# pll_schematic.net
KiCad netlist of a schematic drawn in Altium Designer
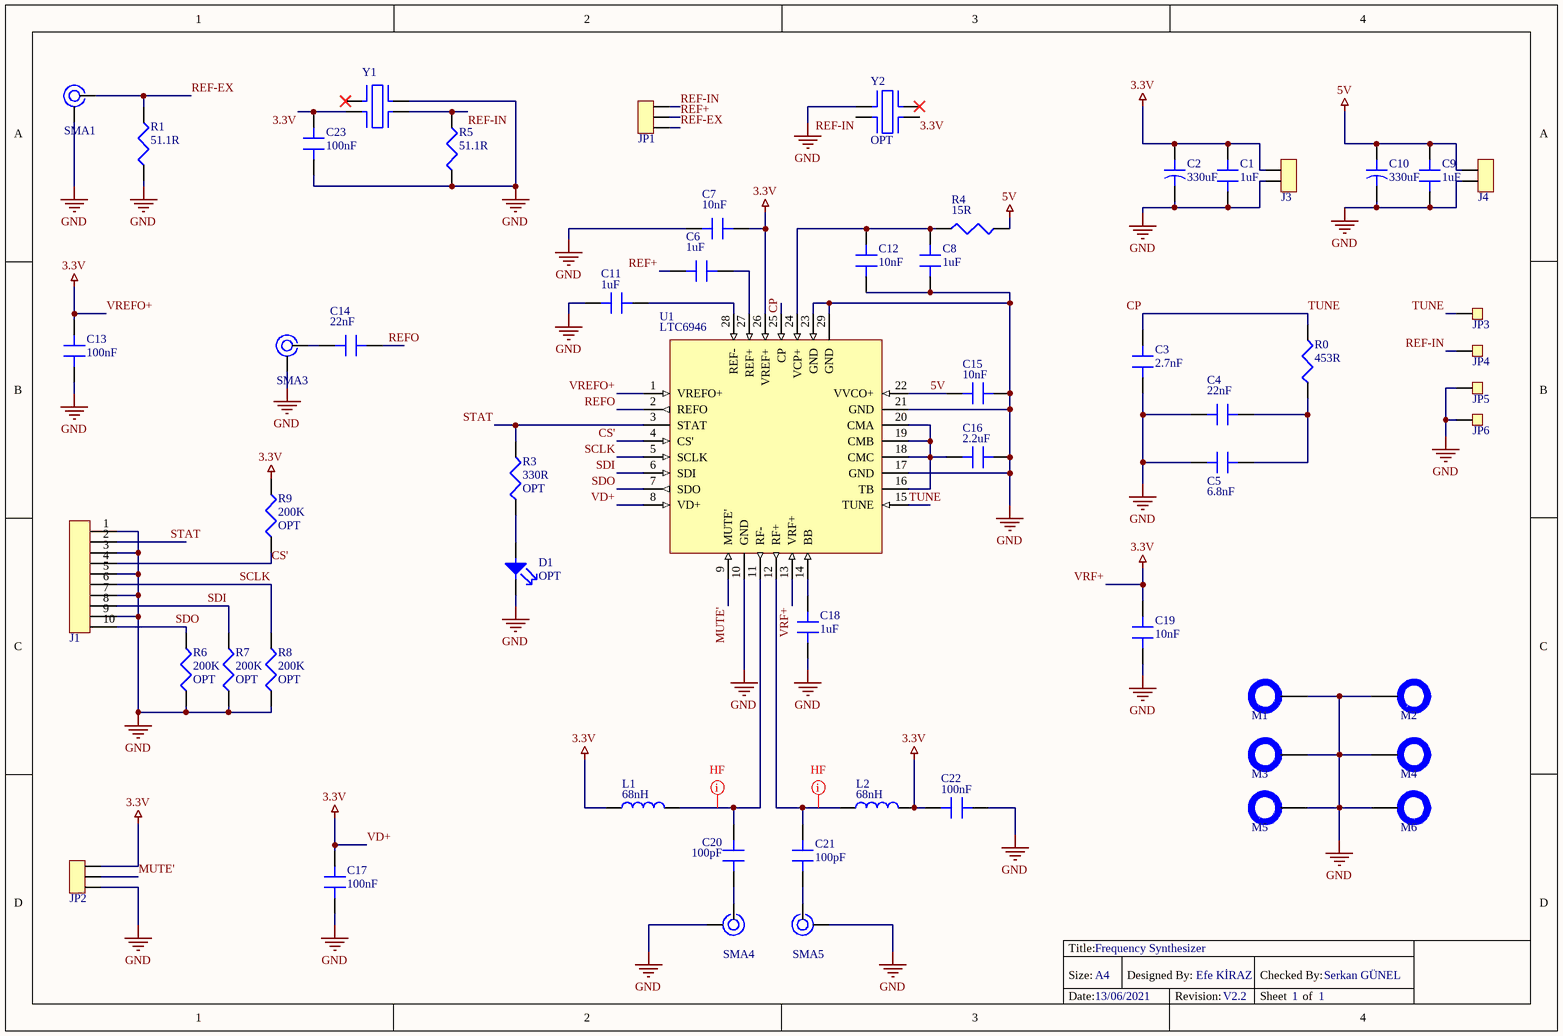
[diagram p0: pll_schematic.SchDoc]

(export (version "E")
  (design (tool "Eeschema 10.0.6"))
  (components
    (comp (ref "C1") (value "1uF") (footprint "C0603") (libsource (lib "pll_schematic_lib") (part "C")))
    (comp (ref "C2") (value "330uF") (footprint "C_TANT_D") (libsource (lib "pll_schematic_lib") (part "CP")))
    (comp (ref "C3") (value "2.7nF") (footprint "C0603") (libsource (lib "pll_schematic_lib") (part "C")))
    (comp (ref "C4") (value "22nF") (footprint "C0603") (libsource (lib "pll_schematic_lib") (part "C")))
    (comp (ref "C5") (value "6.8nF") (footprint "C0603") (libsource (lib "pll_schematic_lib") (part "C")))
    (comp (ref "C6") (value "1uF") (footprint "C0603") (libsource (lib "pll_schematic_lib") (part "C")))
    (comp (ref "C7") (value "10nF") (footprint "C0603") (libsource (lib "pll_schematic_lib") (part "C")))
    (comp (ref "C8") (value "1uF") (footprint "C0603") (libsource (lib "pll_schematic_lib") (part "C")))
    (comp (ref "C9") (value "1uF") (footprint "C0603") (libsource (lib "pll_schematic_lib") (part "C")))
    (comp (ref "C10")
      (value "330uF")
      (footprint "C_TANT_D")
      (libsource (lib "pll_schematic_lib") (part "CP"))
    )
    (comp (ref "C11") (value "1uF") (footprint "C0603") (libsource (lib "pll_schematic_lib") (part "C")))
    (comp (ref "C12") (value "10nF") (footprint "C0603") (libsource (lib "pll_schematic_lib") (part "C")))
    (comp (ref "C13") (value "100nF") (footprint "C0603") (libsource (lib "pll_schematic_lib") (part "C")))
    (comp (ref "C14") (value "22nF") (footprint "C0603") (libsource (lib "pll_schematic_lib") (part "C")))
    (comp (ref "C15") (value "10nF") (footprint "C0603") (libsource (lib "pll_schematic_lib") (part "C")))
    (comp (ref "C16") (value "2.2uF") (footprint "C0805") (libsource (lib "pll_schematic_lib") (part "C")))
    (comp (ref "C17") (value "100nF") (footprint "C0603") (libsource (lib "pll_schematic_lib") (part "C")))
    (comp (ref "C18") (value "1uF") (footprint "C0603") (libsource (lib "pll_schematic_lib") (part "C")))
    (comp (ref "C19") (value "10nF") (footprint "C0603") (libsource (lib "pll_schematic_lib") (part "C")))
    (comp (ref "C20") (value "100pF") (footprint "C0603") (libsource (lib "pll_schematic_lib") (part "C")))
    (comp (ref "C21") (value "100pF") (footprint "C0603") (libsource (lib "pll_schematic_lib") (part "C")))
    (comp (ref "C22") (value "100nF") (footprint "C0603") (libsource (lib "pll_schematic_lib") (part "C")))
    (comp (ref "C23") (value "100nF") (footprint "C0603") (libsource (lib "pll_schematic_lib") (part "C")))
    (comp (ref "D1")
      (value "-")
      (footprint "D0805")
      (fields (field (name "ASSEMBLY") "OPT"))
      (libsource (lib "pll_schematic_lib") (part "LED"))
    )
    (comp (ref "J1")
      (value "-")
      (footprint "IDC-2x05")
      (libsource (lib "pll_schematic_lib") (part "Conn_Gene_1x10"))
    )
    (comp (ref "J3")
      (value "-")
      (footprint "JST_XH_A_2")
      (libsource (lib "pll_schematic_lib") (part "Conn_Gene_1x02"))
    )
    (comp (ref "J4")
      (value "-")
      (footprint "JST_XH_A_2")
      (libsource (lib "pll_schematic_lib") (part "Conn_Gene_1x02"))
    )
    (comp (ref "JP1")
      (value "-")
      (footprint "PIN_HEADER_1x03")
      (libsource (lib "pll_schematic_lib") (part "Pin Header 1x03"))
    )
    (comp (ref "JP2")
      (value "-")
      (footprint "PIN_HEADER_1x03")
      (libsource (lib "pll_schematic_lib") (part "Pin Header 1x03"))
    )
    (comp (ref "JP3")
      (value "-")
      (footprint "PIN_HEADER_1X01")
      (libsource (lib "pll_schematic_lib") (part "Pin Header 1x01"))
    )
    (comp (ref "JP4")
      (value "-")
      (footprint "PIN_HEADER_1X01")
      (libsource (lib "pll_schematic_lib") (part "Pin Header 1x01"))
    )
    (comp (ref "JP5")
      (value "-")
      (footprint "PIN_HEADER_1X01")
      (libsource (lib "pll_schematic_lib") (part "Pin Header 1x01"))
    )
    (comp (ref "JP6")
      (value "-")
      (footprint "PIN_HEADER_1X01")
      (libsource (lib "pll_schematic_lib") (part "Pin Header 1x01"))
    )
    (comp (ref "L1") (value "68nH") (footprint "L0402") (libsource (lib "pll_schematic_lib") (part "L")))
    (comp (ref "L2") (value "68nH") (footprint "L0402") (libsource (lib "pll_schematic_lib") (part "L")))
    (comp (ref "M1")
      (value "MOUNTING_HOLE")
      (footprint "MOUNTING_HOLE_NP_M3")
      (description "Non-Plated")
      (libsource (lib "pll_schematic_lib") (part "MOUNTING_HOLE"))
    )
    (comp (ref "M2")
      (value "MOUNTING_HOLE")
      (footprint "MOUNTING_HOLE_NP_M3")
      (description "Non-Plated")
      (libsource (lib "pll_schematic_lib") (part "MOUNTING_HOLE"))
    )
    (comp (ref "M3")
      (value "MOUNTING_HOLE")
      (footprint "MOUNTING_HOLE_NP_M3")
      (description "Non-Plated")
      (libsource (lib "pll_schematic_lib") (part "MOUNTING_HOLE"))
    )
    (comp (ref "M4")
      (value "MOUNTING_HOLE")
      (footprint "MOUNTING_HOLE_NP_M3")
      (description "Non-Plated")
      (libsource (lib "pll_schematic_lib") (part "MOUNTING_HOLE"))
    )
    (comp (ref "M5")
      (value "MOUNTING_HOLE")
      (footprint "MOUNTING_HOLE_NP_M3")
      (description "Non-Plated")
      (libsource (lib "pll_schematic_lib") (part "MOUNTING_HOLE"))
    )
    (comp (ref "M6")
      (value "MOUNTING_HOLE")
      (footprint "MOUNTING_HOLE_NP_M3")
      (description "Non-Plated")
      (libsource (lib "pll_schematic_lib") (part "MOUNTING_HOLE"))
    )
    (comp (ref "R0") (value "453R") (footprint "R0603") (libsource (lib "pll_schematic_lib") (part "R")))
    (comp (ref "R1") (value "51.1R") (footprint "R0603") (libsource (lib "pll_schematic_lib") (part "R")))
    (comp (ref "R3")
      (value "330R")
      (footprint "R0603")
      (fields (field (name "ASSEMBLY") "OPT"))
      (libsource (lib "pll_schematic_lib") (part "R"))
    )
    (comp (ref "R4") (value "15R") (footprint "R0603") (libsource (lib "pll_schematic_lib") (part "R")))
    (comp (ref "R5") (value "51.1R") (footprint "R0603") (libsource (lib "pll_schematic_lib") (part "R")))
    (comp (ref "R6")
      (value "200K")
      (footprint "R0603")
      (description "OPT")
      (fields (field (name "ASSEMBLY") "OPT"))
      (libsource (lib "pll_schematic_lib") (part "R"))
    )
    (comp (ref "R7")
      (value "200K")
      (footprint "R0603")
      (description "OPT")
      (fields (field (name "ASSEMBLY") "OPT"))
      (libsource (lib "pll_schematic_lib") (part "R"))
    )
    (comp (ref "R8")
      (value "200K")
      (footprint "R0603")
      (description "OPT")
      (fields (field (name "ASSEMBLY") "OPT"))
      (libsource (lib "pll_schematic_lib") (part "R"))
    )
    (comp (ref "R9")
      (value "200K")
      (footprint "R0603")
      (description "OPT")
      (fields (field (name "ASSEMBLY") "OPT"))
      (libsource (lib "pll_schematic_lib") (part "R"))
    )
    (comp (ref "SMA1") (value "-") (footprint "SMA") (libsource (lib "pll_schematic_lib") (part "SMA")))
    (comp (ref "SMA3") (value "-") (footprint "SMA") (libsource (lib "pll_schematic_lib") (part "SMA")))
    (comp (ref "SMA4") (value "-") (footprint "SMA") (libsource (lib "") (part "SMA_1")))
    (comp (ref "SMA5") (value "-") (footprint "SMA") (libsource (lib "pll_schematic_lib") (part "SMA")))
    (comp (ref "U1")
      (value "LTC6946")
      (footprint "QFN50P400X500X80_HS-29N_2")
      (libsource (lib "pll_schematic_lib") (part "LTC6946IUFD-1#PBF-ND"))
    )
    (comp (ref "Y1") (value "-") (footprint "XOSC") (libsource (lib "pll_schematic_lib") (part "OSC")))
    (comp (ref "Y2")
      (value "OPT")
      (footprint "XOSC_SMD")
      (libsource (lib "pll_schematic_lib") (part "OSC_SMD"))
    )
  )
  (nets
    (net (code "1") (name "/CP") (class "Default")
      (node (ref "C3") (pin "2") (pinfunction "-_2") (pintype "passive"))
      (node (ref "JP3") (pin "1") (pinfunction "-_1") (pintype "passive"))
      (node (ref "R0") (pin "2") (pinfunction "-_2") (pintype "passive"))
      (node (ref "U1") (pin "15") (pinfunction "TUNE_15") (pintype "input"))
      (node (ref "U1") (pin "25") (pinfunction "CP_25") (pintype "input"))
    )
    (net (code "2") (name "/CS'") (class "Default")
      (node (ref "J1") (pin "4") (pinfunction "*_4") (pintype "passive"))
      (node (ref "R9") (pin "1") (pinfunction "-_1") (pintype "passive"))
      (node (ref "U1") (pin "4") (pinfunction "CS'_4") (pintype "input"))
    )
    (net (code "3") (name "/MUTE'") (class "Default")
      (node (ref "JP2") (pin "2") (pinfunction "-_2") (pintype "passive"))
      (node (ref "U1") (pin "9") (pinfunction "MUTE'_9") (pintype "input"))
    )
    (net (code "4") (name "/REF+") (class "Default")
      (node (ref "C6") (pin "1") (pinfunction "-_1") (pintype "passive"))
      (node (ref "JP1") (pin "2") (pinfunction "-_2") (pintype "passive"))
    )
    (net (code "5") (name "/REF-EX") (class "Default")
      (node (ref "JP1") (pin "3") (pinfunction "-_3") (pintype "passive"))
      (node (ref "R1") (pin "2") (pinfunction "-_2") (pintype "passive"))
      (node (ref "SMA1") (pin "1") (pinfunction "-_1") (pintype "passive"))
    )
    (net (code "6") (name "/REF-IN") (class "Default")
      (node (ref "JP1") (pin "1") (pinfunction "-_1") (pintype "passive"))
      (node (ref "JP4") (pin "1") (pinfunction "-_1") (pintype "passive"))
      (node (ref "R5") (pin "2") (pinfunction "-_2") (pintype "passive"))
      (node (ref "Y1") (pin "5") (pinfunction "5_5") (pintype "passive"))
      (node (ref "Y2") (pin "3") (pinfunction "3_3") (pintype "passive"))
    )
    (net (code "7") (name "/REFO") (class "Default")
      (node (ref "C14") (pin "2") (pinfunction "-_2") (pintype "passive"))
      (node (ref "U1") (pin "2") (pinfunction "REFO_2") (pintype "output"))
    )
    (net (code "8") (name "/SCLK") (class "Default")
      (node (ref "J1") (pin "6") (pinfunction "*_6") (pintype "passive"))
      (node (ref "R8") (pin "2") (pinfunction "-_2") (pintype "passive"))
      (node (ref "U1") (pin "5") (pinfunction "SCLK_5") (pintype "input"))
    )
    (net (code "9") (name "/SDI") (class "Default")
      (node (ref "J1") (pin "8") (pinfunction "*_8") (pintype "passive"))
      (node (ref "R7") (pin "2") (pinfunction "-_2") (pintype "passive"))
      (node (ref "U1") (pin "6") (pinfunction "SDI_6") (pintype "input"))
    )
    (net (code "10") (name "/SDO") (class "Default")
      (node (ref "J1") (pin "10") (pinfunction "*_10") (pintype "passive"))
      (node (ref "R6") (pin "2") (pinfunction "-_2") (pintype "passive"))
      (node (ref "U1") (pin "7") (pinfunction "SDO_7") (pintype "output"))
    )
    (net (code "11") (name "/STAT") (class "Default")
      (node (ref "J1") (pin "2") (pinfunction "*_2") (pintype "passive"))
      (node (ref "R3") (pin "2") (pinfunction "-_2") (pintype "passive"))
      (node (ref "U1") (pin "3") (pinfunction "STAT_3") (pintype "passive"))
    )
    (net (code "12") (name "3.3V") (class "Default")
      (node (ref "C1") (pin "2") (pinfunction "-_2") (pintype "passive"))
      (node (ref "C13") (pin "2") (pinfunction "-_2") (pintype "passive"))
      (node (ref "C17") (pin "2") (pinfunction "-_2") (pintype "passive"))
      (node (ref "C19") (pin "2") (pinfunction "-_2") (pintype "passive"))
      (node (ref "C2") (pin "1") (pinfunction "-_1") (pintype "passive"))
      (node (ref "C22") (pin "1") (pinfunction "-_1") (pintype "passive"))
      (node (ref "C23") (pin "2") (pinfunction "-_2") (pintype "passive"))
      (node (ref "C7") (pin "1") (pinfunction "-_1") (pintype "passive"))
      (node (ref "J3") (pin "1") (pinfunction "-_1") (pintype "passive"))
      (node (ref "JP2") (pin "1") (pinfunction "-_1") (pintype "passive"))
      (node (ref "L1") (pin "1") (pinfunction "-_1") (pintype "passive"))
      (node (ref "L2") (pin "2") (pinfunction "-_2") (pintype "passive"))
      (node (ref "R9") (pin "2") (pinfunction "-_2") (pintype "passive"))
      (node (ref "U1") (pin "1") (pinfunction "VREFO+_1") (pintype "input"))
      (node (ref "U1") (pin "13") (pinfunction "VRF+_13") (pintype "input"))
      (node (ref "U1") (pin "26") (pinfunction "VREF+_26") (pintype "input"))
      (node (ref "U1") (pin "8") (pinfunction "VD+_8") (pintype "input"))
      (node (ref "Y1") (pin "8") (pinfunction "8_8") (pintype "passive"))
      (node (ref "Y2") (pin "4") (pinfunction "4_4") (pintype "passive"))
    )
    (net (code "13") (name "5V") (class "Default")
      (node (ref "C10") (pin "1") (pinfunction "-_1") (pintype "passive"))
      (node (ref "C15") (pin "1") (pinfunction "-_1") (pintype "passive"))
      (node (ref "C9") (pin "1") (pinfunction "-_1") (pintype "passive"))
      (node (ref "J4") (pin "1") (pinfunction "-_1") (pintype "passive"))
      (node (ref "R4") (pin "2") (pinfunction "-_2") (pintype "passive"))
      (node (ref "U1") (pin "22") (pinfunction "VVCO+_22") (pintype "input"))
    )
    (net (code "14") (name "GND") (class "Default")
      (node (ref "C1") (pin "1") (pinfunction "-_1") (pintype "passive"))
      (node (ref "C10") (pin "2") (pinfunction "-_2") (pintype "passive"))
      (node (ref "C11") (pin "1") (pinfunction "-_1") (pintype "passive"))
      (node (ref "C12") (pin "2") (pinfunction "-_2") (pintype "passive"))
      (node (ref "C13") (pin "1") (pinfunction "-_1") (pintype "passive"))
      (node (ref "C15") (pin "2") (pinfunction "-_2") (pintype "passive"))
      (node (ref "C16") (pin "2") (pinfunction "-_2") (pintype "passive"))
      (node (ref "C17") (pin "1") (pinfunction "-_1") (pintype "passive"))
      (node (ref "C18") (pin "1") (pinfunction "-_1") (pintype "passive"))
      (node (ref "C19") (pin "1") (pinfunction "-_1") (pintype "passive"))
      (node (ref "C2") (pin "2") (pinfunction "-_2") (pintype "passive"))
      (node (ref "C22") (pin "2") (pinfunction "-_2") (pintype "passive"))
      (node (ref "C23") (pin "1") (pinfunction "-_1") (pintype "passive"))
      (node (ref "C3") (pin "1") (pinfunction "-_1") (pintype "passive"))
      (node (ref "C4") (pin "2") (pinfunction "-_2") (pintype "passive"))
      (node (ref "C5") (pin "2") (pinfunction "-_2") (pintype "passive"))
      (node (ref "C7") (pin "2") (pinfunction "-_2") (pintype "passive"))
      (node (ref "C8") (pin "1") (pinfunction "-_1") (pintype "passive"))
      (node (ref "C9") (pin "2") (pinfunction "-_2") (pintype "passive"))
      (node (ref "D1") (pin "C") (pinfunction "C_C") (pintype "passive"))
      (node (ref "J1") (pin "1") (pinfunction "*_1") (pintype "passive"))
      (node (ref "J1") (pin "3") (pinfunction "*_3") (pintype "passive"))
      (node (ref "J1") (pin "5") (pinfunction "*_5") (pintype "passive"))
      (node (ref "J1") (pin "7") (pinfunction "*_7") (pintype "passive"))
      (node (ref "J1") (pin "9") (pinfunction "*_9") (pintype "passive"))
      (node (ref "J3") (pin "2") (pinfunction "-_2") (pintype "passive"))
      (node (ref "J4") (pin "2") (pinfunction "-_2") (pintype "passive"))
      (node (ref "JP2") (pin "3") (pinfunction "-_3") (pintype "passive"))
      (node (ref "JP5") (pin "1") (pinfunction "-_1") (pintype "passive"))
      (node (ref "JP6") (pin "1") (pinfunction "-_1") (pintype "passive"))
      (node (ref "M1") (pin "1") (pinfunction "*_1") (pintype "passive"))
      (node (ref "M2") (pin "1") (pinfunction "*_1") (pintype "passive"))
      (node (ref "M3") (pin "1") (pinfunction "*_1") (pintype "passive"))
      (node (ref "M4") (pin "1") (pinfunction "*_1") (pintype "passive"))
      (node (ref "M5") (pin "1") (pinfunction "*_1") (pintype "passive"))
      (node (ref "M6") (pin "1") (pinfunction "*_1") (pintype "passive"))
      (node (ref "R1") (pin "1") (pinfunction "-_1") (pintype "passive"))
      (node (ref "R5") (pin "1") (pinfunction "-_1") (pintype "passive"))
      (node (ref "R6") (pin "1") (pinfunction "-_1") (pintype "passive"))
      (node (ref "R7") (pin "1") (pinfunction "-_1") (pintype "passive"))
      (node (ref "R8") (pin "1") (pinfunction "-_1") (pintype "passive"))
      (node (ref "SMA1") (pin "2") (pinfunction "-_2") (pintype "passive"))
      (node (ref "SMA3") (pin "2") (pinfunction "-_2") (pintype "passive"))
      (node (ref "SMA4") (pin "2") (pinfunction "-_2") (pintype "passive"))
      (node (ref "SMA5") (pin "2") (pinfunction "-_2") (pintype "passive"))
      (node (ref "U1") (pin "10") (pinfunction "GND_10") (pintype "passive"))
      (node (ref "U1") (pin "17") (pinfunction "GND_17") (pintype "passive"))
      (node (ref "U1") (pin "21") (pinfunction "GND_21") (pintype "passive"))
      (node (ref "U1") (pin "23") (pinfunction "GND_23") (pintype "input"))
      (node (ref "U1") (pin "29") (pinfunction "GND_29") (pintype "passive"))
      (node (ref "Y1") (pin "4") (pinfunction "4_4") (pintype "passive"))
      (node (ref "Y2") (pin "2") (pinfunction "2_2") (pintype "passive"))
    )
    (net (code "15") (name "Net-(C4---Pad1)") (class "Default")
      (node (ref "C4") (pin "1") (pinfunction "-_1") (pintype "passive"))
      (node (ref "C5") (pin "1") (pinfunction "-_1") (pintype "passive"))
      (node (ref "R0") (pin "1") (pinfunction "-_1") (pintype "passive"))
    )
    (net (code "16") (name "Net-(C14---Pad1)") (class "Default")
      (node (ref "C14") (pin "1") (pinfunction "-_1") (pintype "passive"))
      (node (ref "SMA3") (pin "1") (pinfunction "-_1") (pintype "passive"))
    )
    (net (code "17") (name "Net-(C20---Pad1)") (class "Default")
      (node (ref "C20") (pin "1") (pinfunction "-_1") (pintype "passive"))
      (node (ref "SMA4") (pin "1") (pinfunction "-_1") (pintype "passive"))
    )
    (net (code "18") (name "Net-(C21---Pad1)") (class "Default")
      (node (ref "C21") (pin "1") (pinfunction "-_1") (pintype "passive"))
      (node (ref "SMA5") (pin "1") (pinfunction "-_1") (pintype "passive"))
    )
    (net (code "19") (name "Net-(D1-PadA)") (class "Default")
      (node (ref "D1") (pin "A") (pinfunction "A_A") (pintype "passive"))
      (node (ref "R3") (pin "1") (pinfunction "-_1") (pintype "passive"))
    )
    (net (code "20") (name "Net-(U1-BB)") (class "Default")
      (node (ref "C18") (pin "2") (pinfunction "-_2") (pintype "passive"))
      (node (ref "U1") (pin "14") (pinfunction "BB_14") (pintype "input"))
    )
    (net (code "21") (name "Net-(U1-CMA)") (class "Default")
      (node (ref "C16") (pin "1") (pinfunction "-_1") (pintype "passive"))
      (node (ref "U1") (pin "16") (pinfunction "TB_16") (pintype "passive"))
      (node (ref "U1") (pin "18") (pinfunction "CMC_18") (pintype "passive"))
      (node (ref "U1") (pin "19") (pinfunction "CMB_19") (pintype "passive"))
      (node (ref "U1") (pin "20") (pinfunction "CMA_20") (pintype "passive"))
    )
    (net (code "22") (name "Net-(U1-REF+)") (class "Default")
      (node (ref "C6") (pin "2") (pinfunction "-_2") (pintype "passive"))
      (node (ref "U1") (pin "27") (pinfunction "REF+_27") (pintype "input"))
    )
    (net (code "23") (name "Net-(U1-REF-)") (class "Default")
      (node (ref "C11") (pin "2") (pinfunction "-_2") (pintype "passive"))
      (node (ref "U1") (pin "28") (pinfunction "REF-_28") (pintype "input"))
    )
    (net (code "24") (name "Net-(U1-RF+)") (class "Default")
      (node (ref "C21") (pin "2") (pinfunction "-_2") (pintype "passive"))
      (node (ref "L2") (pin "1") (pinfunction "-_1") (pintype "passive"))
      (node (ref "U1") (pin "12") (pinfunction "RF+_12") (pintype "output"))
    )
    (net (code "25") (name "Net-(U1-RF-)") (class "Default")
      (node (ref "C20") (pin "2") (pinfunction "-_2") (pintype "passive"))
      (node (ref "L1") (pin "2") (pinfunction "-_2") (pintype "passive"))
      (node (ref "U1") (pin "11") (pinfunction "RF-_11") (pintype "output"))
    )
    (net (code "26") (name "Net-(U1-VCP+)") (class "Default")
      (node (ref "C12") (pin "1") (pinfunction "-_1") (pintype "passive"))
      (node (ref "C8") (pin "2") (pinfunction "-_2") (pintype "passive"))
      (node (ref "R4") (pin "1") (pinfunction "-_1") (pintype "passive"))
      (node (ref "U1") (pin "24") (pinfunction "VCP+_24") (pintype "input"))
    )
    (net (code "27") (name "unconnected-(Y1-Pad1)") (class "Default")
      (node (ref "Y1") (pin "1") (pinfunction "1_1") (pintype "passive+no_connect"))
    )
    (net (code "28") (name "unconnected-(Y2-Pad1)") (class "Default")
      (node (ref "Y2") (pin "1") (pinfunction "1_1") (pintype "passive+no_connect"))
    )
  )
)
